# Servorino_FT230X_brick.net
KiCad netlist of a schematic drawn in EAGLE
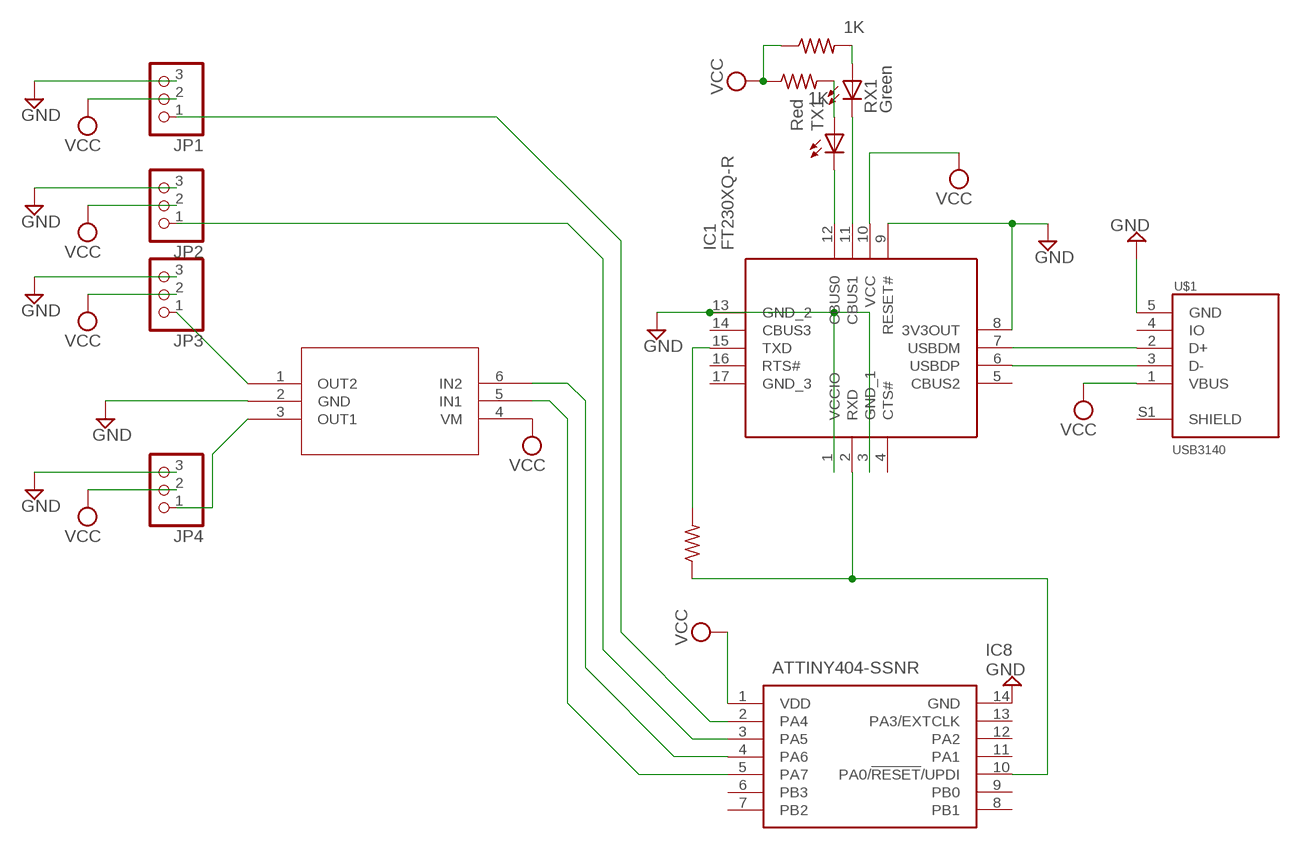
[diagram p0: schematic, sheet 1]

(export (version "E")
  (design (tool "Eeschema 10.0.6"))
  (components
    (comp (ref "IC1")
      (value "FT230XQ-R")
      (footprint "eagle-import:QFN65P400X400X80-17N")
      (fields (field (name "MOUSER_PART_NUMBER") "895-FT230XQ-R"))
      (libsource (lib "eagle-import") (part "FT230XQ-R"))
    )
    (comp (ref "IC8")
      (value "ATTINY404-SSNR")
      (footprint "eagle-import:SOIC127P600X175-14N")
      (fields (field (name "MOUSER_PART_NUMBER") "556-ATTINY404-SSNR"))
      (libsource (lib "eagle-import") (part "ATTINY404-SSNR"))
    )
    (comp (ref "JP1")
      (value "PINHD-1X3")
      (footprint "eagle-import:1X03")
      (libsource (lib "eagle-import") (part "PINHD-1X3"))
    )
    (comp (ref "JP2")
      (value "PINHD-1X3")
      (footprint "eagle-import:1X03")
      (libsource (lib "eagle-import") (part "PINHD-1X3"))
    )
    (comp (ref "JP3")
      (value "PINHD-1X3")
      (footprint "eagle-import:1X03")
      (libsource (lib "eagle-import") (part "PINHD-1X3"))
    )
    (comp (ref "JP4")
      (value "PINHD-1X3")
      (footprint "eagle-import:1X03")
      (libsource (lib "eagle-import") (part "PINHD-1X3"))
    )
    (comp (ref "R4")
      (value "1K")
      (footprint "eagle-import:R0805")
      (libsource (lib "eagle-import") (part "R-US_R0805"))
    )
    (comp (ref "R5")
      (value "1K")
      (footprint "eagle-import:R0805")
      (libsource (lib "eagle-import") (part "R-US_R0805"))
    )
    (comp (ref "R6")
      (value "470")
      (footprint "eagle-import:R0805")
      (libsource (lib "eagle-import") (part "R-US_R0805"))
    )
    (comp (ref "RX1")
      (value "Green")
      (footprint "eagle-import:CHIP-LED0805")
      (libsource (lib "eagle-import") (part "LEDCHIP-LED0805"))
    )
    (comp (ref "TX1")
      (value "Red")
      (footprint "eagle-import:CHIP-LED0805")
      (libsource (lib "eagle-import") (part "LEDCHIP-LED0805"))
    )
    (comp (ref "U$1")
      (value "USB3140")
      (footprint "eagle-import:USB3140-30-0170-0-C")
      (libsource (lib "eagle-import") (part "USB3140"))
    )
    (comp (ref "U2")
      (value "TPM16050-S6TRSOT23-6_TPK-L")
      (footprint "eagle-import:SOT23-6_TPK-L")
      (fields
        (field (name "MANUFACTURER_PART_NUMBER") "TPM16050-S6TR")
        (field (name "COPYRIGHT") "Copyright (C) 2025 Ultra Librarian. All rights reserved.")
      )
      (libsource (lib "eagle-import") (part "TPM16050-S6TRSOT23-6_TPK-L"))
    )
  )
  (nets
    (net (code "1") (name "GND") (class "Default")
      (node (ref "IC1") (pin "1") (pinfunction "VCCIO_1") (pintype "bidirectional"))
      (node (ref "IC1") (pin "13") (pinfunction "GND_2_13") (pintype "bidirectional"))
      (node (ref "IC1") (pin "3") (pinfunction "GND_1_3") (pintype "bidirectional"))
      (node (ref "IC1") (pin "8") (pinfunction "3V3OUT_8") (pintype "bidirectional"))
      (node (ref "IC1") (pin "9") (pinfunction "RESET#_9") (pintype "bidirectional"))
      (node (ref "IC8") (pin "14") (pinfunction "GND_14") (pintype "bidirectional"))
      (node (ref "JP1") (pin "3") (pinfunction "3_3") (pintype "passive"))
      (node (ref "JP2") (pin "3") (pinfunction "3_3") (pintype "passive"))
      (node (ref "JP3") (pin "3") (pinfunction "3_3") (pintype "passive"))
      (node (ref "JP4") (pin "3") (pinfunction "3_3") (pintype "passive"))
      (node (ref "U$1") (pin "5") (pinfunction "GND_5") (pintype "passive"))
      (node (ref "U2") (pin "2") (pinfunction "GND_2") (pintype "passive"))
    )
    (net (code "2") (name "Net-(IC1-CBUS0)") (class "Default")
      (node (ref "IC1") (pin "12") (pinfunction "CBUS0_12") (pintype "bidirectional"))
      (node (ref "TX1") (pin "C") (pinfunction "C_C") (pintype "passive"))
    )
    (net (code "3") (name "Net-(IC1-CBUS1)") (class "Default")
      (node (ref "IC1") (pin "11") (pinfunction "CBUS1_11") (pintype "bidirectional"))
      (node (ref "RX1") (pin "C") (pinfunction "C_C") (pintype "passive"))
    )
    (net (code "4") (name "Net-(IC1-RXD)") (class "Default")
      (node (ref "IC1") (pin "2") (pinfunction "RXD_2") (pintype "bidirectional"))
      (node (ref "IC8") (pin "10") (pinfunction "PA0/~{RESET}/UPDI_10") (pintype "bidirectional"))
      (node (ref "R6") (pin "1") (pinfunction "1_1") (pintype "passive"))
    )
    (net (code "5") (name "Net-(IC1-TXD)") (class "Default")
      (node (ref "IC1") (pin "15") (pinfunction "TXD_15") (pintype "bidirectional"))
      (node (ref "R6") (pin "2") (pinfunction "2_2") (pintype "passive"))
    )
    (net (code "6") (name "Net-(IC1-USBDM)") (class "Default")
      (node (ref "IC1") (pin "7") (pinfunction "USBDM_7") (pintype "bidirectional"))
      (node (ref "U$1") (pin "2") (pinfunction "D+_2") (pintype "passive"))
    )
    (net (code "7") (name "Net-(IC1-USBDP)") (class "Default")
      (node (ref "IC1") (pin "6") (pinfunction "USBDP_6") (pintype "bidirectional"))
      (node (ref "U$1") (pin "3") (pinfunction "D-_3") (pintype "passive"))
    )
    (net (code "8") (name "Net-(IC8-PA4)") (class "Default")
      (node (ref "IC8") (pin "2") (pinfunction "PA4_2") (pintype "bidirectional"))
      (node (ref "JP1") (pin "1") (pinfunction "1_1") (pintype "passive"))
    )
    (net (code "9") (name "Net-(IC8-PA5)") (class "Default")
      (node (ref "IC8") (pin "3") (pinfunction "PA5_3") (pintype "bidirectional"))
      (node (ref "JP2") (pin "1") (pinfunction "1_1") (pintype "passive"))
    )
    (net (code "10") (name "Net-(IC8-PA6)") (class "Default")
      (node (ref "IC8") (pin "4") (pinfunction "PA6_4") (pintype "bidirectional"))
      (node (ref "U2") (pin "6") (pinfunction "IN2_6") (pintype "input"))
    )
    (net (code "11") (name "Net-(IC8-PA7)") (class "Default")
      (node (ref "IC8") (pin "5") (pinfunction "PA7_5") (pintype "bidirectional"))
      (node (ref "U2") (pin "5") (pinfunction "IN1_5") (pintype "input"))
    )
    (net (code "12") (name "Net-(R4-Pad2)") (class "Default")
      (node (ref "R4") (pin "2") (pinfunction "2_2") (pintype "passive"))
      (node (ref "RX1") (pin "A") (pinfunction "A_A") (pintype "passive"))
    )
    (net (code "13") (name "Net-(R5-Pad2)") (class "Default")
      (node (ref "R5") (pin "2") (pinfunction "2_2") (pintype "passive"))
      (node (ref "TX1") (pin "A") (pinfunction "A_A") (pintype "passive"))
    )
    (net (code "14") (name "Net-(U2-OUT1)") (class "Default")
      (node (ref "JP4") (pin "1") (pinfunction "1_1") (pintype "passive"))
      (node (ref "U2") (pin "3") (pinfunction "OUT1_3") (pintype "output"))
    )
    (net (code "15") (name "Net-(U2-OUT2)") (class "Default")
      (node (ref "JP3") (pin "1") (pinfunction "1_1") (pintype "passive"))
      (node (ref "U2") (pin "1") (pinfunction "OUT2_1") (pintype "output"))
    )
    (net (code "16") (name "VCC") (class "Default")
      (node (ref "IC1") (pin "10") (pinfunction "VCC_10") (pintype "bidirectional"))
      (node (ref "IC8") (pin "1") (pinfunction "VDD_1") (pintype "bidirectional"))
      (node (ref "JP1") (pin "2") (pinfunction "2_2") (pintype "passive"))
      (node (ref "JP2") (pin "2") (pinfunction "2_2") (pintype "passive"))
      (node (ref "JP3") (pin "2") (pinfunction "2_2") (pintype "passive"))
      (node (ref "JP4") (pin "2") (pinfunction "2_2") (pintype "passive"))
      (node (ref "R4") (pin "1") (pinfunction "1_1") (pintype "passive"))
      (node (ref "R5") (pin "1") (pinfunction "1_1") (pintype "passive"))
      (node (ref "U$1") (pin "1") (pinfunction "VBUS_1") (pintype "passive"))
      (node (ref "U2") (pin "4") (pinfunction "VM_4") (pintype "power_in"))
    )
    (net (code "17") (name "unconnected-(IC1-CBUS2-Pad5)") (class "Default")
      (node (ref "IC1") (pin "5") (pinfunction "CBUS2_5") (pintype "bidirectional"))
    )
    (net (code "18") (name "unconnected-(IC1-CBUS3-Pad14)") (class "Default")
      (node (ref "IC1") (pin "14") (pinfunction "CBUS3_14") (pintype "bidirectional"))
    )
    (net (code "19") (name "unconnected-(IC1-CTS#-Pad4)") (class "Default")
      (node (ref "IC1") (pin "4") (pinfunction "CTS#_4") (pintype "bidirectional"))
    )
    (net (code "20") (name "unconnected-(IC1-GND_3-Pad17)") (class "Default")
      (node (ref "IC1") (pin "17") (pinfunction "GND_3_17") (pintype "bidirectional"))
    )
    (net (code "21") (name "unconnected-(IC1-RTS#-Pad16)") (class "Default")
      (node (ref "IC1") (pin "16") (pinfunction "RTS#_16") (pintype "bidirectional"))
    )
    (net (code "22") (name "unconnected-(IC8-PA1-Pad11)") (class "Default")
      (node (ref "IC8") (pin "11") (pinfunction "PA1_11") (pintype "bidirectional"))
    )
    (net (code "23") (name "unconnected-(IC8-PA2-Pad12)") (class "Default")
      (node (ref "IC8") (pin "12") (pinfunction "PA2_12") (pintype "bidirectional"))
    )
    (net (code "24") (name "unconnected-(IC8-PA3{slash}EXTCLK-Pad13)") (class "Default")
      (node (ref "IC8") (pin "13") (pinfunction "PA3/EXTCLK_13") (pintype "bidirectional"))
    )
    (net (code "25") (name "unconnected-(IC8-PB0-Pad9)") (class "Default")
      (node (ref "IC8") (pin "9") (pinfunction "PB0_9") (pintype "bidirectional"))
    )
    (net (code "26") (name "unconnected-(IC8-PB1-Pad8)") (class "Default")
      (node (ref "IC8") (pin "8") (pinfunction "PB1_8") (pintype "bidirectional"))
    )
    (net (code "27") (name "unconnected-(IC8-PB2-Pad7)") (class "Default")
      (node (ref "IC8") (pin "7") (pinfunction "PB2_7") (pintype "bidirectional"))
    )
    (net (code "28") (name "unconnected-(IC8-PB3-Pad6)") (class "Default")
      (node (ref "IC8") (pin "6") (pinfunction "PB3_6") (pintype "bidirectional"))
    )
    (net (code "29") (name "unconnected-(U$1-IO-Pad4)") (class "Default")
      (node (ref "U$1") (pin "4") (pinfunction "IO_4") (pintype "passive"))
    )
    (net (code "30") (name "unconnected-(U$1-SHIELD-PadS1)") (class "Default")
      (node (ref "U$1") (pin "S1") (pinfunction "SHIELD_S1") (pintype "passive"))
    )
  )
)
